# tire_temp.net
KiCad netlist of a schematic drawn in EAGLE
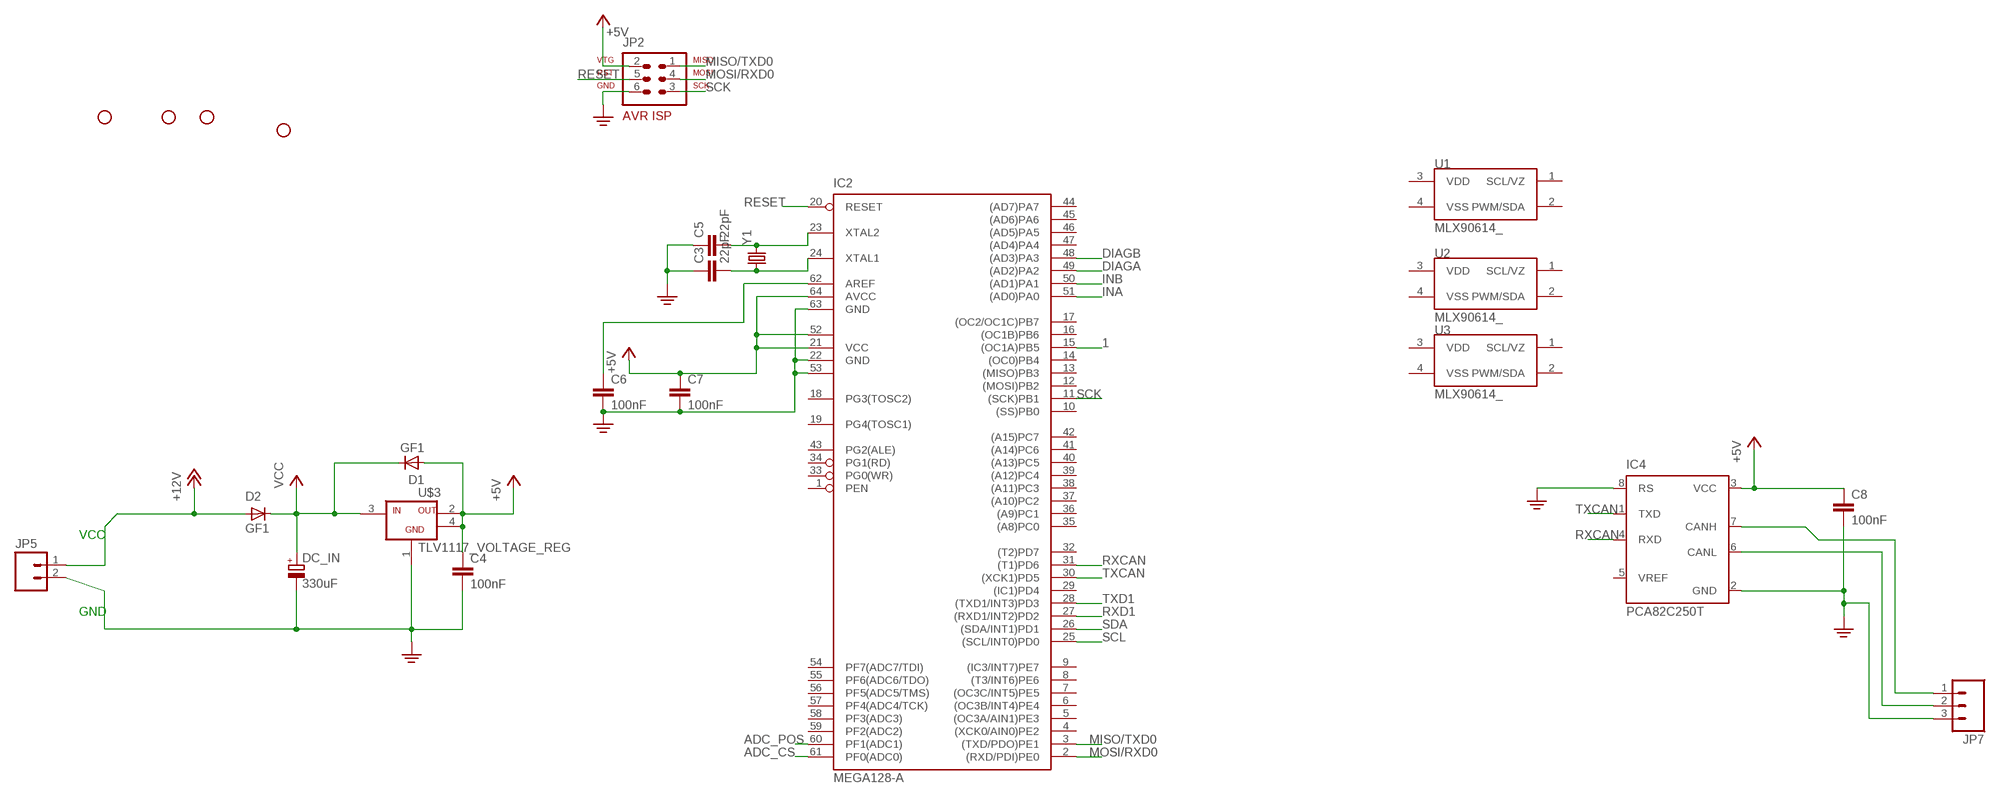
[diagram p0: schematic, sheet 1]

(export (version "E")
  (design (tool "Eeschema 10.0.6"))
  (components
    (comp (ref "C3")
      (value "22pF")
      (footprint "eagle-import:C0603K")
      (libsource (lib "eagle-import") (part "C-EUC0603K"))
    )
    (comp (ref "C4")
      (value "100nF")
      (footprint "eagle-import:C0603K")
      (libsource (lib "eagle-import") (part "C-EUC0603K"))
    )
    (comp (ref "C5")
      (value "22pF")
      (footprint "eagle-import:C0603K")
      (libsource (lib "eagle-import") (part "C-EUC0603K"))
    )
    (comp (ref "C6")
      (value "100nF")
      (footprint "eagle-import:C0603K")
      (libsource (lib "eagle-import") (part "C-EUC0603K"))
    )
    (comp (ref "C7")
      (value "100nF")
      (footprint "eagle-import:C0603K")
      (libsource (lib "eagle-import") (part "C-EUC0603K"))
    )
    (comp (ref "C8")
      (value "100nF")
      (footprint "eagle-import:C0603K")
      (libsource (lib "eagle-import") (part "C-EUC0603K"))
    )
    (comp (ref "D1")
      (value "GF1")
      (footprint "eagle-import:SMA-DO214AC")
      (libsource (lib "eagle-import") (part "GF1"))
    )
    (comp (ref "D2")
      (value "GF1")
      (footprint "eagle-import:SMA-DO214AC")
      (libsource (lib "eagle-import") (part "GF1"))
    )
    (comp (ref "DC_IN")
      (value "330uF")
      (footprint "eagle-import:E15-5")
      (libsource (lib "eagle-import") (part "CPOL-EUE15-5AXIAL"))
    )
    (comp (ref "IC2")
      (value "MEGA128-A")
      (footprint "eagle-import:TQFP64")
      (libsource (lib "eagle-import") (part "MEGA128-A"))
    )
    (comp (ref "IC4")
      (value "PCA82C250T")
      (footprint "eagle-import:SO8")
      (libsource (lib "eagle-import") (part "PCA82C250T"))
    )
    (comp (ref "JP1")
      (value "STAND-OFF")
      (footprint "eagle-import:STAND-OFF")
      (libsource (lib "eagle-import") (part "STAND-OFF"))
    )
    (comp (ref "JP2")
      (value "AVR-ISP-6")
      (footprint "eagle-import:AVR-ISP-6")
      (libsource (lib "eagle-import") (part "AVR-ISP-6"))
    )
    (comp (ref "JP3")
      (value "STAND-OFF")
      (footprint "eagle-import:STAND-OFF")
      (libsource (lib "eagle-import") (part "STAND-OFF"))
    )
    (comp (ref "JP4")
      (value "STAND-OFF")
      (footprint "eagle-import:STAND-OFF")
      (libsource (lib "eagle-import") (part "STAND-OFF"))
    )
    (comp (ref "JP5")
      (value "M02-JST-2MM-SMT")
      (footprint "eagle-import:JST-2-SMD")
      (libsource (lib "eagle-import") (part "M02-JST-2MM-SMT"))
    )
    (comp (ref "JP6")
      (value "STAND-OFF")
      (footprint "eagle-import:STAND-OFF")
      (libsource (lib "eagle-import") (part "STAND-OFF"))
    )
    (comp (ref "JP7")
      (value "M03")
      (footprint "eagle-import:JST-3-SMD")
      (libsource (lib "eagle-import") (part "M03"))
    )
    (comp (ref "U$3")
      (value "TLV1117_VOLTAGE_REG")
      (footprint "eagle-import:SOT-232")
      (libsource (lib "eagle-import") (part "TLV1117_VOLTAGE_REG"))
    )
    (comp (ref "U1")
      (value "MLX90614_")
      (footprint "eagle-import:TO-39")
      (libsource (lib "eagle-import") (part "MLX90614_"))
    )
    (comp (ref "U2")
      (value "MLX90614_")
      (footprint "eagle-import:TO-39")
      (libsource (lib "eagle-import") (part "MLX90614_"))
    )
    (comp (ref "U3")
      (value "MLX90614_")
      (footprint "eagle-import:TO-39")
      (libsource (lib "eagle-import") (part "MLX90614_"))
    )
    (comp (ref "Y1")
      (value "CRYSTAL5X3")
      (footprint "eagle-import:CRYSTAL-SMD-5X3")
      (libsource (lib "eagle-import") (part "CRYSTAL5X3"))
    )
  )
  (nets
    (net (code "1") (name "+5V") (class "Default")
      (node (ref "C4") (pin "1") (pinfunction "1_1") (pintype "passive"))
      (node (ref "C7") (pin "1") (pinfunction "1_1") (pintype "passive"))
      (node (ref "C8") (pin "1") (pinfunction "1_1") (pintype "passive"))
      (node (ref "D1") (pin "A") (pinfunction "A_A") (pintype "passive"))
      (node (ref "IC2") (pin "21") (pinfunction "VCC_21") (pintype "power_in"))
      (node (ref "IC2") (pin "52") (pinfunction "VCC1_52") (pintype "power_in"))
      (node (ref "IC2") (pin "64") (pinfunction "AVCC_64") (pintype "power_in"))
      (node (ref "IC4") (pin "3") (pinfunction "VCC_3") (pintype "power_in"))
      (node (ref "JP2") (pin "2") (pinfunction "2_2") (pintype "passive"))
      (node (ref "U$3") (pin "2") (pinfunction "VOUT_2") (pintype "passive"))
      (node (ref "U$3") (pin "4") (pinfunction "OUT2_4") (pintype "passive"))
    )
    (net (code "2") (name "+12V") (class "Default")
      (node (ref "D2") (pin "A") (pinfunction "A_A") (pintype "passive"))
      (node (ref "JP5") (pin "1") (pinfunction "2_1") (pintype "passive"))
    )
    (net (code "3") (name "/1") (class "Default")
      (node (ref "IC2") (pin "15") (pinfunction "(OC1A)PB5_15") (pintype "bidirectional"))
    )
    (net (code "4") (name "/ADC_CS") (class "Default")
      (node (ref "IC2") (pin "61") (pinfunction "PF0(ADC0)_61") (pintype "input"))
    )
    (net (code "5") (name "/ADC_POS") (class "Default")
      (node (ref "IC2") (pin "60") (pinfunction "PF1(ADC1)_60") (pintype "input"))
    )
    (net (code "6") (name "/DIAGA") (class "Default")
      (node (ref "IC2") (pin "49") (pinfunction "(AD2)PA2_49") (pintype "bidirectional"))
    )
    (net (code "7") (name "/DIAGB") (class "Default")
      (node (ref "IC2") (pin "48") (pinfunction "(AD3)PA3_48") (pintype "bidirectional"))
    )
    (net (code "8") (name "/INA") (class "Default")
      (node (ref "IC2") (pin "51") (pinfunction "(AD0)PA0_51") (pintype "bidirectional"))
    )
    (net (code "9") (name "/INB") (class "Default")
      (node (ref "IC2") (pin "50") (pinfunction "(AD1)PA1_50") (pintype "bidirectional"))
    )
    (net (code "10") (name "/MISO{slash}TXD0") (class "Default")
      (node (ref "IC2") (pin "3") (pinfunction "(TXD/PDO)PE1_3") (pintype "bidirectional"))
      (node (ref "JP2") (pin "1") (pinfunction "1_1") (pintype "passive"))
    )
    (net (code "11") (name "/MOSI{slash}RXD0") (class "Default")
      (node (ref "IC2") (pin "2") (pinfunction "(RXD/PDI)PE0_2") (pintype "bidirectional"))
      (node (ref "JP2") (pin "4") (pinfunction "4_4") (pintype "passive"))
    )
    (net (code "12") (name "/RESET") (class "Default")
      (node (ref "IC2") (pin "20") (pinfunction "RESET_20") (pintype "input"))
      (node (ref "JP2") (pin "5") (pinfunction "5_5") (pintype "passive"))
    )
    (net (code "13") (name "/RXCAN") (class "Default")
      (node (ref "IC2") (pin "31") (pinfunction "(T1)PD6_31") (pintype "bidirectional"))
      (node (ref "IC4") (pin "4") (pinfunction "RXD_4") (pintype "output"))
    )
    (net (code "14") (name "/RXD1") (class "Default")
      (node (ref "IC2") (pin "27") (pinfunction "(RXD1/INT2)PD2_27") (pintype "bidirectional"))
    )
    (net (code "15") (name "/SCK") (class "Default")
      (node (ref "IC2") (pin "11") (pinfunction "(SCK)PB1_11") (pintype "bidirectional"))
      (node (ref "JP2") (pin "3") (pinfunction "3_3") (pintype "passive"))
    )
    (net (code "16") (name "/SCL") (class "Default")
      (node (ref "IC2") (pin "25") (pinfunction "(SCL/INT0)PD0_25") (pintype "bidirectional"))
    )
    (net (code "17") (name "/SDA") (class "Default")
      (node (ref "IC2") (pin "26") (pinfunction "(SDA/INT1)PD1_26") (pintype "bidirectional"))
    )
    (net (code "18") (name "/TXCAN") (class "Default")
      (node (ref "IC2") (pin "30") (pinfunction "(XCK1)PD5_30") (pintype "bidirectional"))
      (node (ref "IC4") (pin "1") (pinfunction "TXD_1") (pintype "input"))
    )
    (net (code "19") (name "/TXD1") (class "Default")
      (node (ref "IC2") (pin "28") (pinfunction "(TXD1/INT3)PD3_28") (pintype "bidirectional"))
    )
    (net (code "20") (name "Net-(IC2-AREF)") (class "Default")
      (node (ref "C6") (pin "1") (pinfunction "1_1") (pintype "passive"))
      (node (ref "IC2") (pin "62") (pinfunction "AREF_62") (pintype "passive"))
    )
    (net (code "21") (name "Net-(IC2-XTAL1)") (class "Default")
      (node (ref "C3") (pin "2") (pinfunction "2_2") (pintype "passive"))
      (node (ref "IC2") (pin "24") (pinfunction "XTAL1_24") (pintype "bidirectional"))
      (node (ref "Y1") (pin "1") (pinfunction "1_1") (pintype "passive"))
    )
    (net (code "22") (name "Net-(IC2-XTAL2)") (class "Default")
      (node (ref "C5") (pin "2") (pinfunction "2_2") (pintype "passive"))
      (node (ref "IC2") (pin "23") (pinfunction "XTAL2_23") (pintype "bidirectional"))
      (node (ref "Y1") (pin "3") (pinfunction "2_3") (pintype "passive"))
    )
    (net (code "23") (name "Net-(IC4-CANH)") (class "Default")
      (node (ref "IC4") (pin "7") (pinfunction "CANH_7") (pintype "bidirectional"))
      (node (ref "JP7") (pin "1") (pinfunction "1_1") (pintype "passive"))
    )
    (net (code "24") (name "Net-(IC4-CANL)") (class "Default")
      (node (ref "IC4") (pin "6") (pinfunction "CANL_6") (pintype "bidirectional"))
      (node (ref "JP7") (pin "2") (pinfunction "2_2") (pintype "passive"))
    )
    (net (code "25") (name "PE") (class "Default")
      (node (ref "C3") (pin "1") (pinfunction "1_1") (pintype "passive"))
      (node (ref "C4") (pin "2") (pinfunction "2_2") (pintype "passive"))
      (node (ref "C5") (pin "1") (pinfunction "1_1") (pintype "passive"))
      (node (ref "C6") (pin "2") (pinfunction "2_2") (pintype "passive"))
      (node (ref "C7") (pin "2") (pinfunction "2_2") (pintype "passive"))
      (node (ref "C8") (pin "2") (pinfunction "2_2") (pintype "passive"))
      (node (ref "DC_IN") (pin "-") (pinfunction "-_-") (pintype "passive"))
      (node (ref "IC2") (pin "22") (pinfunction "GND_22") (pintype "power_in"))
      (node (ref "IC2") (pin "53") (pinfunction "GND1_53") (pintype "power_in"))
      (node (ref "IC2") (pin "63") (pinfunction "GND_63") (pintype "power_in"))
      (node (ref "IC4") (pin "2") (pinfunction "GND_2") (pintype "power_in"))
      (node (ref "IC4") (pin "8") (pinfunction "RS_8") (pintype "input"))
      (node (ref "JP2") (pin "6") (pinfunction "6_6") (pintype "passive"))
      (node (ref "JP5") (pin "2") (pinfunction "1_2") (pintype "passive"))
      (node (ref "JP7") (pin "3") (pinfunction "3_3") (pintype "passive"))
      (node (ref "U$3") (pin "1") (pinfunction "GND_1") (pintype "passive"))
    )
    (net (code "26") (name "VCC") (class "Default")
      (node (ref "D1") (pin "K") (pinfunction "C_K") (pintype "passive"))
      (node (ref "D2") (pin "K") (pinfunction "C_K") (pintype "passive"))
      (node (ref "DC_IN") (pin "+") (pinfunction "+_+") (pintype "passive"))
      (node (ref "U$3") (pin "3") (pinfunction "VIN_3") (pintype "passive"))
    )
    (net (code "27") (name "unconnected-(IC2-(A8)PC0-Pad35)") (class "Default")
      (node (ref "IC2") (pin "35") (pinfunction "(A8)PC0_35") (pintype "output"))
    )
    (net (code "28") (name "unconnected-(IC2-(A9)PC1-Pad36)") (class "Default")
      (node (ref "IC2") (pin "36") (pinfunction "(A9)PC1_36") (pintype "output"))
    )
    (net (code "29") (name "unconnected-(IC2-(A10)PC2-Pad37)") (class "Default")
      (node (ref "IC2") (pin "37") (pinfunction "(A10)PC2_37") (pintype "output"))
    )
    (net (code "30") (name "unconnected-(IC2-(A11)PC3-Pad38)") (class "Default")
      (node (ref "IC2") (pin "38") (pinfunction "(A11)PC3_38") (pintype "output"))
    )
    (net (code "31") (name "unconnected-(IC2-(A12)PC4-Pad39)") (class "Default")
      (node (ref "IC2") (pin "39") (pinfunction "(A12)PC4_39") (pintype "output"))
    )
    (net (code "32") (name "unconnected-(IC2-(A13)PC5-Pad40)") (class "Default")
      (node (ref "IC2") (pin "40") (pinfunction "(A13)PC5_40") (pintype "output"))
    )
    (net (code "33") (name "unconnected-(IC2-(A14)PC6-Pad41)") (class "Default")
      (node (ref "IC2") (pin "41") (pinfunction "(A14)PC6_41") (pintype "output"))
    )
    (net (code "34") (name "unconnected-(IC2-(A15)PC7-Pad42)") (class "Default")
      (node (ref "IC2") (pin "42") (pinfunction "(A15)PC7_42") (pintype "output"))
    )
    (net (code "35") (name "unconnected-(IC2-(AD4)PA4-Pad47)") (class "Default")
      (node (ref "IC2") (pin "47") (pinfunction "(AD4)PA4_47") (pintype "bidirectional"))
    )
    (net (code "36") (name "unconnected-(IC2-(AD5)PA5-Pad46)") (class "Default")
      (node (ref "IC2") (pin "46") (pinfunction "(AD5)PA5_46") (pintype "bidirectional"))
    )
    (net (code "37") (name "unconnected-(IC2-(AD6)PA6-Pad45)") (class "Default")
      (node (ref "IC2") (pin "45") (pinfunction "(AD6)PA6_45") (pintype "bidirectional"))
    )
    (net (code "38") (name "unconnected-(IC2-(AD7)PA7-Pad44)") (class "Default")
      (node (ref "IC2") (pin "44") (pinfunction "(AD7)PA7_44") (pintype "bidirectional"))
    )
    (net (code "39") (name "unconnected-(IC2-(IC1)PD4-Pad29)") (class "Default")
      (node (ref "IC2") (pin "29") (pinfunction "(IC1)PD4_29") (pintype "bidirectional"))
    )
    (net (code "40") (name "unconnected-(IC2-(IC3{slash}INT7)PE7-Pad9)") (class "Default")
      (node (ref "IC2") (pin "9") (pinfunction "(IC3/INT7)PE7_9") (pintype "bidirectional"))
    )
    (net (code "41") (name "unconnected-(IC2-(MISO)PB3-Pad13)") (class "Default")
      (node (ref "IC2") (pin "13") (pinfunction "(MISO)PB3_13") (pintype "bidirectional"))
    )
    (net (code "42") (name "unconnected-(IC2-(MOSI)PB2-Pad12)") (class "Default")
      (node (ref "IC2") (pin "12") (pinfunction "(MOSI)PB2_12") (pintype "bidirectional"))
    )
    (net (code "43") (name "unconnected-(IC2-(OC0)PB4-Pad14)") (class "Default")
      (node (ref "IC2") (pin "14") (pinfunction "(OC0)PB4_14") (pintype "bidirectional"))
    )
    (net (code "44") (name "unconnected-(IC2-(OC1B)PB6-Pad16)") (class "Default")
      (node (ref "IC2") (pin "16") (pinfunction "(OC1B)PB6_16") (pintype "bidirectional"))
    )
    (net (code "45") (name "unconnected-(IC2-(OC2{slash}OC1C)PB7-Pad17)") (class "Default")
      (node (ref "IC2") (pin "17") (pinfunction "(OC2/OC1C)PB7_17") (pintype "bidirectional"))
    )
    (net (code "46") (name "unconnected-(IC2-(OC3A{slash}AIN1)PE3-Pad5)") (class "Default")
      (node (ref "IC2") (pin "5") (pinfunction "(OC3A/AIN1)PE3_5") (pintype "bidirectional"))
    )
    (net (code "47") (name "unconnected-(IC2-(OC3B{slash}INT4)PE4-Pad6)") (class "Default")
      (node (ref "IC2") (pin "6") (pinfunction "(OC3B/INT4)PE4_6") (pintype "bidirectional"))
    )
    (net (code "48") (name "unconnected-(IC2-(OC3C{slash}INT5)PE5-Pad7)") (class "Default")
      (node (ref "IC2") (pin "7") (pinfunction "(OC3C/INT5)PE5_7") (pintype "bidirectional"))
    )
    (net (code "49") (name "unconnected-(IC2-(SS)PB0-Pad10)") (class "Default")
      (node (ref "IC2") (pin "10") (pinfunction "(SS)PB0_10") (pintype "bidirectional"))
    )
    (net (code "50") (name "unconnected-(IC2-(T2)PD7-Pad32)") (class "Default")
      (node (ref "IC2") (pin "32") (pinfunction "(T2)PD7_32") (pintype "bidirectional"))
    )
    (net (code "51") (name "unconnected-(IC2-(T3{slash}INT6)PE6-Pad8)") (class "Default")
      (node (ref "IC2") (pin "8") (pinfunction "(T3/INT6)PE6_8") (pintype "bidirectional"))
    )
    (net (code "52") (name "unconnected-(IC2-(XCK0{slash}AIN0)PE2-Pad4)") (class "Default")
      (node (ref "IC2") (pin "4") (pinfunction "(XCK0/AIN0)PE2_4") (pintype "bidirectional"))
    )
    (net (code "53") (name "unconnected-(IC2-PEN-Pad1)") (class "Default")
      (node (ref "IC2") (pin "1") (pinfunction "PEN_1") (pintype "input"))
    )
    (net (code "54") (name "unconnected-(IC2-PF2(ADC2)-Pad59)") (class "Default")
      (node (ref "IC2") (pin "59") (pinfunction "PF2(ADC2)_59") (pintype "input"))
    )
    (net (code "55") (name "unconnected-(IC2-PF3(ADC3)-Pad58)") (class "Default")
      (node (ref "IC2") (pin "58") (pinfunction "PF3(ADC3)_58") (pintype "input"))
    )
    (net (code "56") (name "unconnected-(IC2-PF4(ADC4{slash}TCK)-Pad57)") (class "Default")
      (node (ref "IC2") (pin "57") (pinfunction "PF4(ADC4/TCK)_57") (pintype "input"))
    )
    (net (code "57") (name "unconnected-(IC2-PF5(ADC5{slash}TMS)-Pad56)") (class "Default")
      (node (ref "IC2") (pin "56") (pinfunction "PF5(ADC5/TMS)_56") (pintype "input"))
    )
    (net (code "58") (name "unconnected-(IC2-PF6(ADC6{slash}TDO)-Pad55)") (class "Default")
      (node (ref "IC2") (pin "55") (pinfunction "PF6(ADC6/TDO)_55") (pintype "input"))
    )
    (net (code "59") (name "unconnected-(IC2-PF7(ADC7{slash}TDI)-Pad54)") (class "Default")
      (node (ref "IC2") (pin "54") (pinfunction "PF7(ADC7/TDI)_54") (pintype "input"))
    )
    (net (code "60") (name "unconnected-(IC2-PG0(WR)-Pad33)") (class "Default")
      (node (ref "IC2") (pin "33") (pinfunction "PG0(WR)_33") (pintype "bidirectional"))
    )
    (net (code "61") (name "unconnected-(IC2-PG1(RD)-Pad34)") (class "Default")
      (node (ref "IC2") (pin "34") (pinfunction "PG1(RD)_34") (pintype "bidirectional"))
    )
    (net (code "62") (name "unconnected-(IC2-PG2(ALE)-Pad43)") (class "Default")
      (node (ref "IC2") (pin "43") (pinfunction "PG2(ALE)_43") (pintype "bidirectional"))
    )
    (net (code "63") (name "unconnected-(IC2-PG3(TOSC2)-Pad18)") (class "Default")
      (node (ref "IC2") (pin "18") (pinfunction "PG3(TOSC2)_18") (pintype "bidirectional"))
    )
    (net (code "64") (name "unconnected-(IC2-PG4(TOSC1)-Pad19)") (class "Default")
      (node (ref "IC2") (pin "19") (pinfunction "PG4(TOSC1)_19") (pintype "bidirectional"))
    )
    (net (code "65") (name "unconnected-(IC4-VREF-Pad5)") (class "Default")
      (node (ref "IC4") (pin "5") (pinfunction "VREF_5") (pintype "output"))
    )
    (net (code "66") (name "unconnected-(U1-PWM{slash}SDA-Pad2)") (class "Default")
      (node (ref "U1") (pin "2") (pinfunction "PWM/SDA_2") (pintype "bidirectional"))
    )
    (net (code "67") (name "unconnected-(U1-SCL{slash}VZ-Pad1)") (class "Default")
      (node (ref "U1") (pin "1") (pinfunction "SCL/VZ_1") (pintype "bidirectional"))
    )
    (net (code "68") (name "unconnected-(U1-VDD-Pad3)") (class "Default")
      (node (ref "U1") (pin "3") (pinfunction "VDD_3") (pintype "bidirectional"))
    )
    (net (code "69") (name "unconnected-(U1-VSS-Pad4)") (class "Default")
      (node (ref "U1") (pin "4") (pinfunction "VSS_4") (pintype "bidirectional"))
    )
    (net (code "70") (name "unconnected-(U2-PWM{slash}SDA-Pad2)") (class "Default")
      (node (ref "U2") (pin "2") (pinfunction "PWM/SDA_2") (pintype "bidirectional"))
    )
    (net (code "71") (name "unconnected-(U2-SCL{slash}VZ-Pad1)") (class "Default")
      (node (ref "U2") (pin "1") (pinfunction "SCL/VZ_1") (pintype "bidirectional"))
    )
    (net (code "72") (name "unconnected-(U2-VDD-Pad3)") (class "Default")
      (node (ref "U2") (pin "3") (pinfunction "VDD_3") (pintype "bidirectional"))
    )
    (net (code "73") (name "unconnected-(U2-VSS-Pad4)") (class "Default")
      (node (ref "U2") (pin "4") (pinfunction "VSS_4") (pintype "bidirectional"))
    )
    (net (code "74") (name "unconnected-(U3-PWM{slash}SDA-Pad2)") (class "Default")
      (node (ref "U3") (pin "2") (pinfunction "PWM/SDA_2") (pintype "bidirectional"))
    )
    (net (code "75") (name "unconnected-(U3-SCL{slash}VZ-Pad1)") (class "Default")
      (node (ref "U3") (pin "1") (pinfunction "SCL/VZ_1") (pintype "bidirectional"))
    )
    (net (code "76") (name "unconnected-(U3-VDD-Pad3)") (class "Default")
      (node (ref "U3") (pin "3") (pinfunction "VDD_3") (pintype "bidirectional"))
    )
    (net (code "77") (name "unconnected-(U3-VSS-Pad4)") (class "Default")
      (node (ref "U3") (pin "4") (pinfunction "VSS_4") (pintype "bidirectional"))
    )
  )
)
